# Autoswitch.net
KiCad netlist of a schematic drawn in Altium Designer
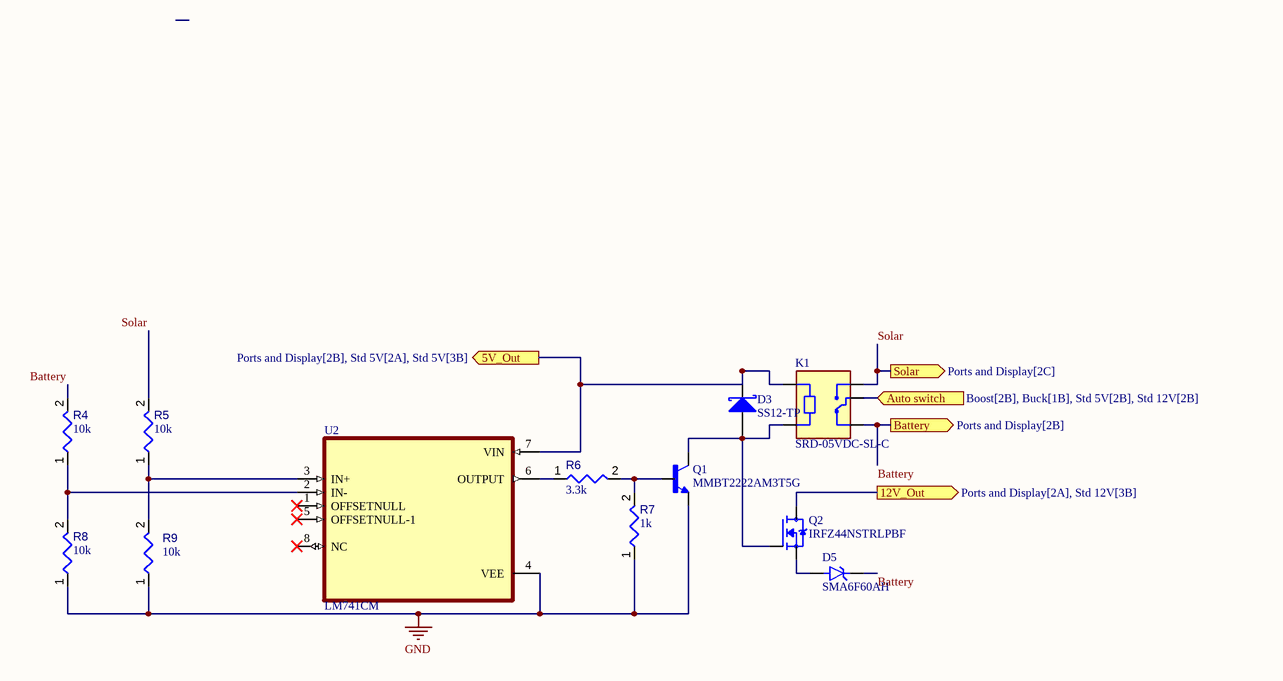
[diagram p0: Autoswitch.SchDoc]

(export (version "E")
  (design (tool "Eeschema 10.0.6"))
  (components
    (comp (ref "D3")
      (value "SS12-TP")
      (footprint "MCC-DO-214AC-2_V")
      (description "Schottky Rectifier, 20 V, 1 A, -55 to 125 degC, 2-Pin DO-214AC, RoHS, Tape and Reel")
      (fields (field (name "MANUFACTURER") "Micro Commercial Components"))
      (libsource (lib "Vedant Ashtankar") (part "DSKY-AK-2"))
    )
    (comp (ref "D5")
      (value "SMA6F60AH")
      (footprint "SODFL5226X100N")
      (description "600W, 70.6V, 5%, Unidirectional, TVS")
      (fields (field (name "MF") "Taiwan Semiconductor"))
      (libsource (lib "Vedant Ashtankar") (part "SMA6F60AH"))
    )
    (comp (ref "K1")
      (value "SRD-05VDC-SL-C")
      (footprint "RELAY_SRD-05VDC-SL-C")
      (fields (field (name "MF") "Songle Relay"))
      (libsource (lib "Vedant Ashtankar") (part "SRD-05VDC-SL-C"))
    )
    (comp (ref "Q1")
      (value "MMBT2222AM3T5G")
      (footprint "SOT95P240X120-3N")
      (description "BJT, SOT-23, 40V, 600mA, NPN, 0.25W, 150°C")
      (fields (field (name "MP") "MMBT2222A") (field (name "MF") "Diotec Semiconductor"))
      (libsource (lib "Vedant Ashtankar") (part "MMBT2222A"))
    )
    (comp (ref "Q2")
      (value "IRFZ44NSTRLPBF")
      (footprint "DPAK254P1524X483-3N")
      (description "RoHS Compliant")
      (fields (field (name "MF") "Infineon Technologies"))
      (libsource (lib "Vedant Ashtankar") (part "IRFZ44NSTRLPBF"))
    )
    (comp (ref "R4")
      (value "10k")
      (footprint "RESC0805(2012)_L")
      (description "1K 0.125W 5% 0805 (2012 Metric)  SMD")
      (fields (field (name "TOLERANCE") "5%") (field (name "POWER") "125mW"))
      (libsource (lib "Vedant Ashtankar") (part "1KR5J"))
    )
    (comp (ref "R5")
      (value "10k")
      (footprint "RESC0805(2012)_L")
      (description "1K 0.125W 5% 0805 (2012 Metric)  SMD")
      (fields (field (name "TOLERANCE") "5%") (field (name "POWER") "125mW"))
      (libsource (lib "Vedant Ashtankar") (part "1KR5J"))
    )
    (comp (ref "R6")
      (value "3.3k")
      (footprint "RESC0805(2012)_L")
      (description "1K 0.125W 5% 0805 (2012 Metric)  SMD")
      (fields (field (name "TOLERANCE") "5%") (field (name "POWER") "125mW"))
      (libsource (lib "Vedant Ashtankar") (part "1KR5J"))
    )
    (comp (ref "R7")
      (value "1k")
      (footprint "RESC0805(2012)_L")
      (description "1K 0.125W 5% 0805 (2012 Metric)  SMD")
      (fields (field (name "TOLERANCE") "5%") (field (name "POWER") "125mW"))
      (libsource (lib "Vedant Ashtankar") (part "1KR5J"))
    )
    (comp (ref "R8")
      (value "10k")
      (footprint "RESC0805(2012)_L")
      (description "1K 0.125W 5% 0805 (2012 Metric)  SMD")
      (fields (field (name "TOLERANCE") "5%") (field (name "POWER") "125mW"))
      (libsource (lib "Vedant Ashtankar") (part "1KR5J"))
    )
    (comp (ref "R9")
      (value "10k")
      (footprint "RESC0805(2012)_L")
      (description "1K 0.125W 5% 0805 (2012 Metric)  SMD")
      (fields (field (name "TOLERANCE") "5%") (field (name "POWER") "125mW"))
      (libsource (lib "Vedant Ashtankar") (part "1KR5J"))
    )
    (comp (ref "U2")
      (value "LM741CM")
      (footprint "SOIC127P599X175-8N")
      (description "General Purpose Amplifier 1 Circuit 8-SOIC")
      (fields (field (name "MF") "Fairchild Semiconductor"))
      (libsource (lib "Vedant Ashtankar") (part "LM741CM"))
    )
  )
  (nets
    (net (code "1") (name "/5V_Out") (class "Default")
      (node (ref "D3") (pin "2") (pinfunction "K_2") (pintype "passive"))
      (node (ref "K1") (pin "A1") (pinfunction "A1_A1") (pintype "passive"))
      (node (ref "U2") (pin "7") (pinfunction "VIN_7") (pintype "input"))
    )
    (net (code "2") (name "/12V_Out") (class "Default")
      (node (ref "Q2") (pin "2") (pinfunction "D_2") (pintype "passive"))
    )
    (net (code "3") (name "/Auto switch") (class "Default")
      (node (ref "K1") (pin "COM") (pinfunction "COM_COM") (pintype "passive"))
    )
    (net (code "4") (name "/Battery") (class "Default")
      (node (ref "D5") (pin "1") (pinfunction "K_1") (pintype "passive"))
      (node (ref "K1") (pin "NC") (pinfunction "NC_NC") (pintype "passive"))
      (node (ref "R4") (pin "2") (pinfunction "2_2") (pintype "passive"))
    )
    (net (code "5") (name "/Solar") (class "Default")
      (node (ref "K1") (pin "NO") (pinfunction "NO_NO") (pintype "passive"))
      (node (ref "R5") (pin "2") (pinfunction "2_2") (pintype "passive"))
    )
    (net (code "6") (name "GND") (class "Default")
      (node (ref "Q1") (pin "2") (pinfunction "E_2") (pintype "passive"))
      (node (ref "R7") (pin "1") (pinfunction "1_1") (pintype "passive"))
      (node (ref "R8") (pin "1") (pinfunction "1_1") (pintype "passive"))
      (node (ref "R9") (pin "1") (pinfunction "1_1") (pintype "passive"))
      (node (ref "U2") (pin "4") (pinfunction "VEE_4") (pintype "power_in"))
    )
    (net (code "7") (name "Net-(D3-A)") (class "Default")
      (node (ref "D3") (pin "1") (pinfunction "A_1") (pintype "passive"))
      (node (ref "K1") (pin "A2") (pinfunction "A2_A2") (pintype "passive"))
      (node (ref "Q1") (pin "3") (pinfunction "C_3") (pintype "passive"))
      (node (ref "Q2") (pin "1") (pinfunction "G_1") (pintype "passive"))
    )
    (net (code "8") (name "Net-(D5-A)") (class "Default")
      (node (ref "D5") (pin "2") (pinfunction "A_2") (pintype "passive"))
      (node (ref "Q2") (pin "3") (pinfunction "S_3") (pintype "passive"))
    )
    (net (code "9") (name "Net-(Q1-B)") (class "Default")
      (node (ref "Q1") (pin "1") (pinfunction "B_1") (pintype "passive"))
      (node (ref "R6") (pin "2") (pinfunction "2_2") (pintype "passive"))
      (node (ref "R7") (pin "2") (pinfunction "2_2") (pintype "passive"))
    )
    (net (code "10") (name "Net-(U2-IN+)") (class "Default")
      (node (ref "R5") (pin "1") (pinfunction "1_1") (pintype "passive"))
      (node (ref "R9") (pin "2") (pinfunction "2_2") (pintype "passive"))
      (node (ref "U2") (pin "3") (pinfunction "IN+_3") (pintype "input"))
    )
    (net (code "11") (name "Net-(U2-IN-)") (class "Default")
      (node (ref "R4") (pin "1") (pinfunction "1_1") (pintype "passive"))
      (node (ref "R8") (pin "2") (pinfunction "2_2") (pintype "passive"))
      (node (ref "U2") (pin "2") (pinfunction "IN-_2") (pintype "input"))
    )
    (net (code "12") (name "Net-(U2-OUTPUT)") (class "Default")
      (node (ref "R6") (pin "1") (pinfunction "1_1") (pintype "passive"))
      (node (ref "U2") (pin "6") (pinfunction "OUTPUT_6") (pintype "output"))
    )
    (net (code "13") (name "unconnected-(U2-NC-Pad8)") (class "Default")
      (node (ref "U2") (pin "8") (pinfunction "NC_8") (pintype "bidirectional+no_connect"))
    )
    (net (code "14") (name "unconnected-(U2-OFFSETNULL-1-Pad5)") (class "Default")
      (node (ref "U2") (pin "5") (pinfunction "OFFSETNULL-1_5") (pintype "input+no_connect"))
    )
    (net (code "15") (name "unconnected-(U2-OFFSETNULL-Pad1)") (class "Default")
      (node (ref "U2") (pin "1") (pinfunction "OFFSETNULL_1") (pintype "input+no_connect"))
    )
  )
)
